# humidity_v2.net
KiCad netlist of a schematic drawn in EAGLE
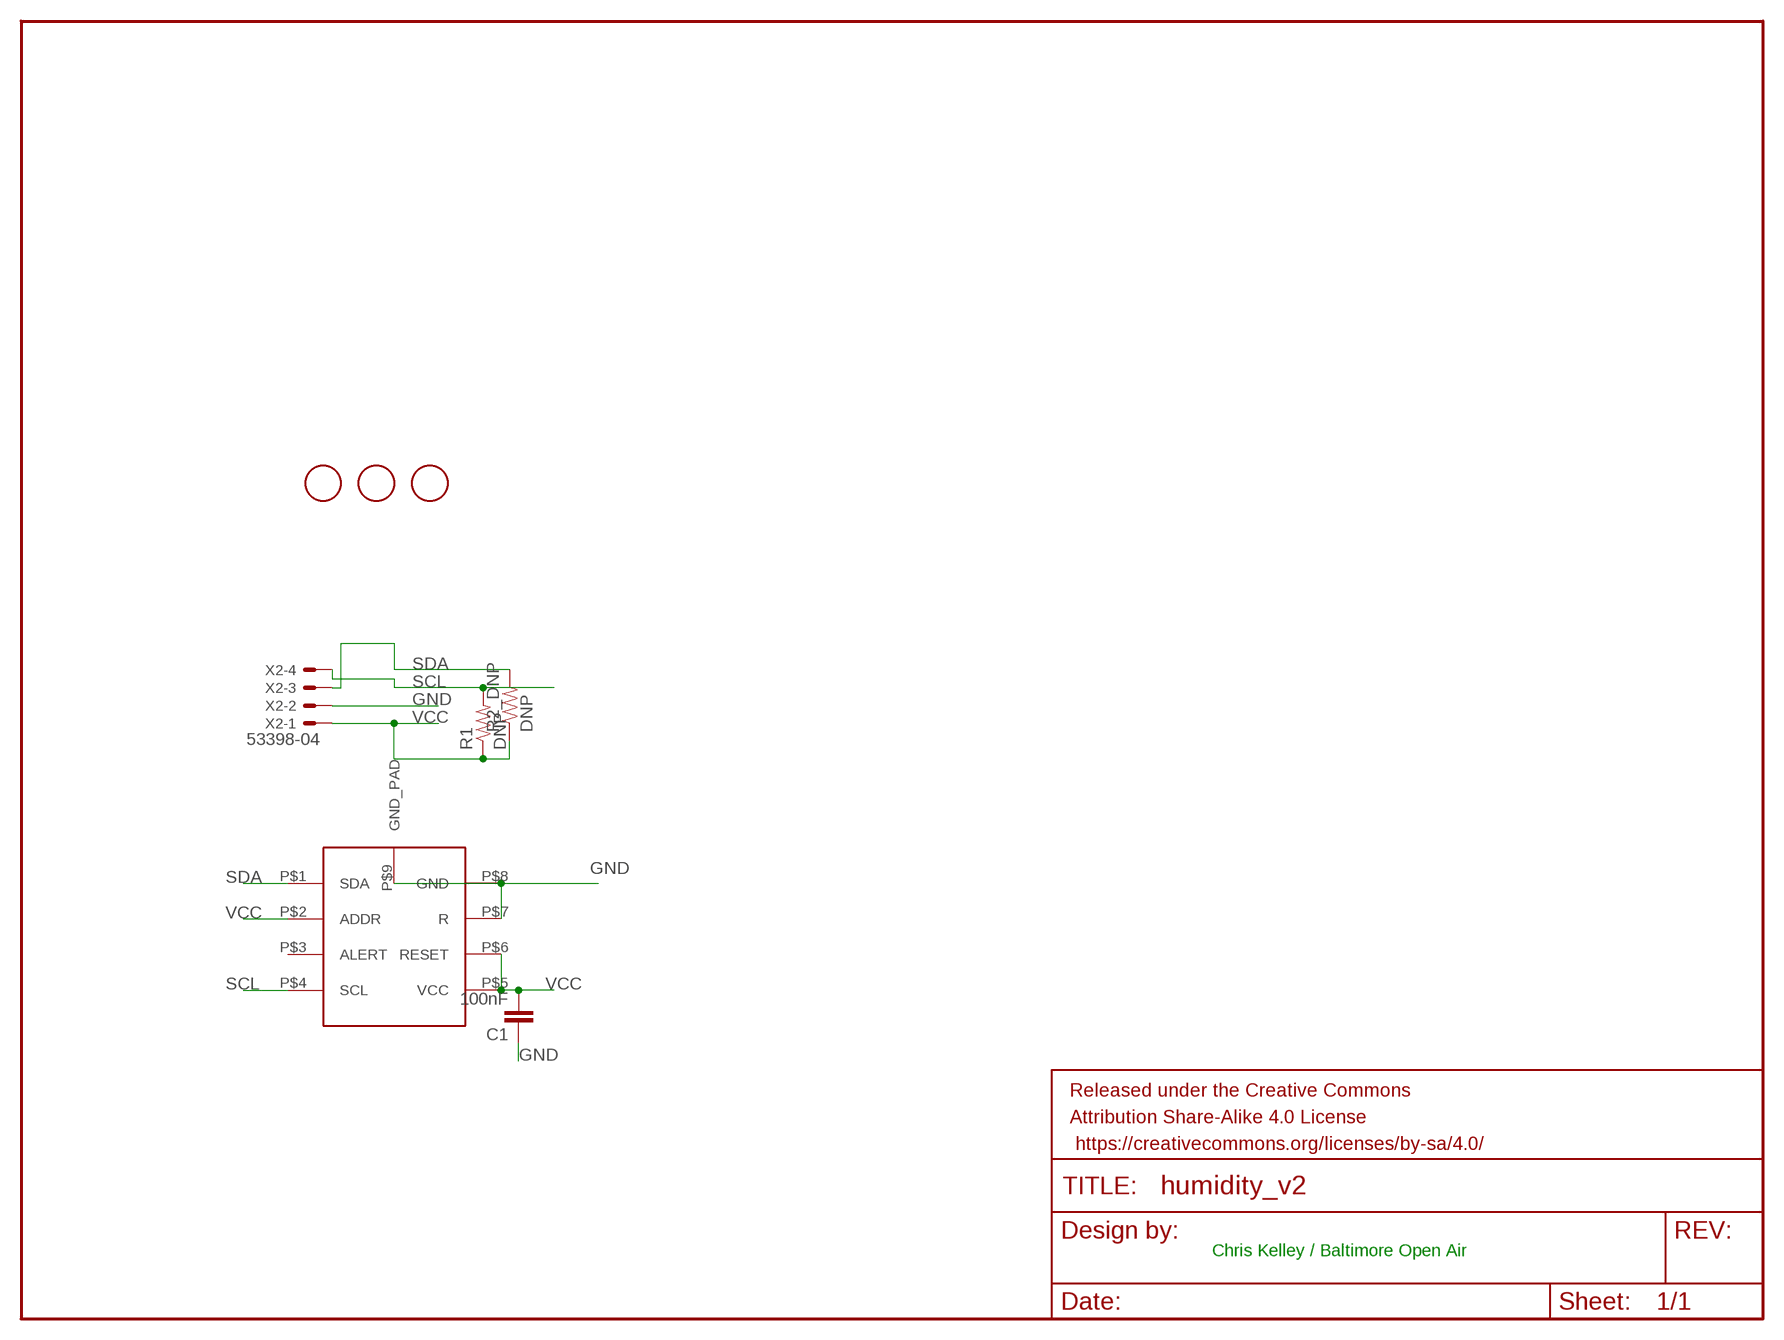
[diagram p0: schematic, sheet 1]

(export (version "E")
  (design (tool "Eeschema 10.0.6"))
  (components
    (comp (ref "C1")
      (value "100nF")
      (footprint "eagle-import:0603-CAP")
      (libsource (lib "eagle-import") (part "CAP0603-CAP"))
    )
    (comp (ref "FRAME1")
      (value "FRAME-LETTER")
      (footprint "eagle-import:CREATIVE_COMMONS")
      (libsource (lib "eagle-import") (part "FRAME-LETTER"))
    )
    (comp (ref "R1")
      (value "DNP")
      (footprint "eagle-import:0603-RES")
      (libsource (lib "eagle-import") (part "RESISTOR0603-RES"))
    )
    (comp (ref "R2_DNP")
      (value "DNP")
      (footprint "eagle-import:0603-RES")
      (libsource (lib "eagle-import") (part "RESISTOR0603-RES"))
    )
    (comp (ref "U$1")
      (value "SHT31-D")
      (footprint "eagle-import:SHT31-D")
      (libsource (lib "eagle-import") (part "SHT31-D"))
    )
    (comp (ref "U$3")
      (value "FIDUCIAL")
      (footprint "eagle-import:FIDUCIAL_1MM")
      (libsource (lib "eagle-import") (part "FIDUCIAL"))
    )
    (comp (ref "U$6")
      (value "FIDUCIAL")
      (footprint "eagle-import:FIDUCIAL_1MM")
      (libsource (lib "eagle-import") (part "FIDUCIAL"))
    )
    (comp (ref "U$7")
      (value "FIDUCIAL")
      (footprint "eagle-import:FIDUCIAL_1MM")
      (libsource (lib "eagle-import") (part "FIDUCIAL"))
    )
    (comp (ref "X2")
      (value "53398-04")
      (footprint "eagle-import:53398-04")
      (libsource (lib "eagle-import") (part "53?-04398"))
    )
  )
  (nets
    (net (code "1") (name "/GND") (class "Default")
      (node (ref "C1") (pin "1") (pinfunction "1_1") (pintype "passive"))
      (node (ref "U$1") (pin "P$7") (pinfunction "R_P$7") (pintype "bidirectional"))
      (node (ref "U$1") (pin "P$8") (pinfunction "GND_P$8") (pintype "bidirectional"))
      (node (ref "U$1") (pin "P$9") (pinfunction "GND_PAD_P$9") (pintype "bidirectional"))
      (node (ref "X2") (pin "2") (pinfunction "S_2") (pintype "passive"))
    )
    (net (code "2") (name "/SCL") (class "Default")
      (node (ref "R1") (pin "2") (pinfunction "2_2") (pintype "passive"))
      (node (ref "U$1") (pin "P$4") (pinfunction "SCL_P$4") (pintype "bidirectional"))
      (node (ref "X2") (pin "4") (pinfunction "S_4") (pintype "passive"))
    )
    (net (code "3") (name "/SDA") (class "Default")
      (node (ref "R2_DNP") (pin "2") (pinfunction "2_2") (pintype "passive"))
      (node (ref "U$1") (pin "P$1") (pinfunction "SDA_P$1") (pintype "bidirectional"))
      (node (ref "X2") (pin "3") (pinfunction "S_3") (pintype "passive"))
    )
    (net (code "4") (name "/VCC") (class "Default")
      (node (ref "C1") (pin "2") (pinfunction "2_2") (pintype "passive"))
      (node (ref "R1") (pin "1") (pinfunction "1_1") (pintype "passive"))
      (node (ref "R2_DNP") (pin "1") (pinfunction "1_1") (pintype "passive"))
      (node (ref "U$1") (pin "P$2") (pinfunction "ADDR_P$2") (pintype "bidirectional"))
      (node (ref "U$1") (pin "P$5") (pinfunction "VCC_P$5") (pintype "bidirectional"))
      (node (ref "U$1") (pin "P$6") (pinfunction "RESET_P$6") (pintype "bidirectional"))
      (node (ref "X2") (pin "1") (pinfunction "S_1") (pintype "passive"))
    )
    (net (code "5") (name "unconnected-(U$1-ALERT-PadP$3)") (class "Default")
      (node (ref "U$1") (pin "P$3") (pinfunction "ALERT_P$3") (pintype "bidirectional"))
    )
  )
)
